# BMS_MCUV1_1.net
KiCad netlist of a schematic drawn in EAGLE
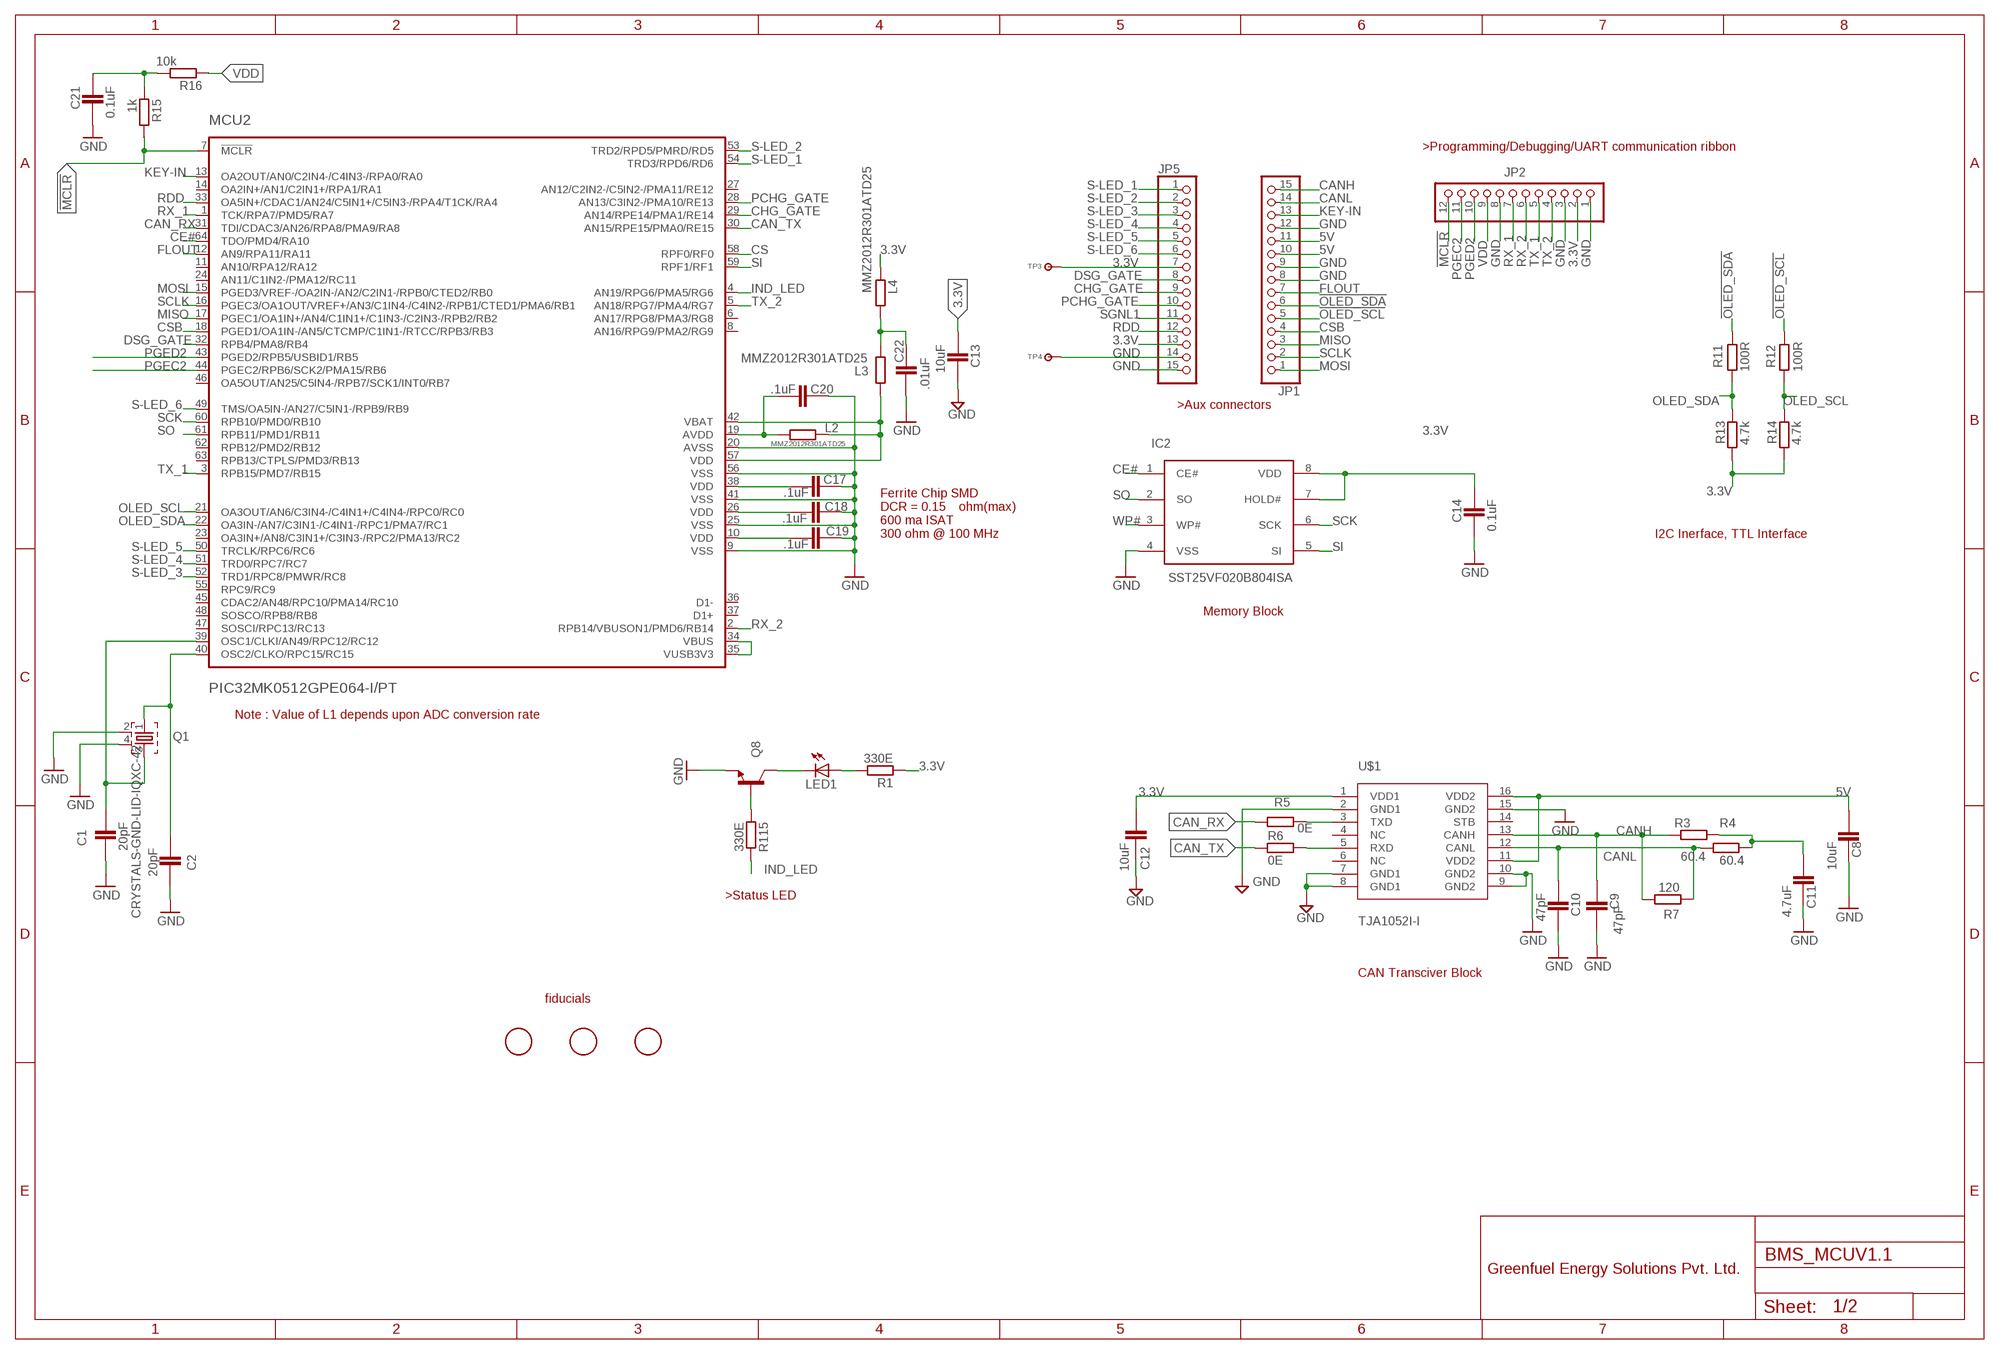
[diagram p0: schematic, sheet 1]

(export (version "E")
  (design (tool "Eeschema 10.0.6"))
  (components
    (comp (ref "C1")
      (value "20pF")
      (footprint "eagle-import:CAPC1005X60N")
      (libsource (lib "eagle-import") (part "CAPACITOR_0402"))
    )
    (comp (ref "C2")
      (value "20pF")
      (footprint "eagle-import:CAPC1005X60N")
      (libsource (lib "eagle-import") (part "CAPACITOR_0402"))
    )
    (comp (ref "C8")
      (value "10uF")
      (footprint "eagle-import:CAPC1005X60N")
      (libsource (lib "eagle-import") (part "CAPACITOR_0402"))
    )
    (comp (ref "C9")
      (value "47pF")
      (footprint "eagle-import:CAPC1005X60N")
      (libsource (lib "eagle-import") (part "CAPACITOR_0402"))
    )
    (comp (ref "C10")
      (value "47pF")
      (footprint "eagle-import:CAPC1005X60N")
      (libsource (lib "eagle-import") (part "CAPACITOR_0402"))
    )
    (comp (ref "C11")
      (value "4.7uF")
      (footprint "eagle-import:CAPC1005X60N")
      (libsource (lib "eagle-import") (part "CAPACITOR_0402"))
    )
    (comp (ref "C12")
      (value "10uF")
      (footprint "eagle-import:CAPC1005X60N")
      (libsource (lib "eagle-import") (part "CAPACITOR_0402"))
    )
    (comp (ref "C13")
      (value "10uF")
      (footprint "eagle-import:CAPC1005X60N")
      (libsource (lib "eagle-import") (part "CAPACITOR_0402"))
    )
    (comp (ref "C14")
      (value "0.1uF")
      (footprint "eagle-import:CAPC1005X60N")
      (libsource (lib "eagle-import") (part "CAPACITOR_0402"))
    )
    (comp (ref "C17")
      (value ".1uF")
      (footprint "eagle-import:CAPC1005X60N")
      (libsource (lib "eagle-import") (part "CAPACITOR_0402"))
    )
    (comp (ref "C18")
      (value ".1uF")
      (footprint "eagle-import:CAPC1005X60N")
      (libsource (lib "eagle-import") (part "CAPACITOR_0402"))
    )
    (comp (ref "C19")
      (value ".1uF")
      (footprint "eagle-import:CAPC1005X60N")
      (libsource (lib "eagle-import") (part "CAPACITOR_0402"))
    )
    (comp (ref "C20")
      (value ".1uF")
      (footprint "eagle-import:CAPC1005X60N")
      (libsource (lib "eagle-import") (part "CAPACITOR_0402"))
    )
    (comp (ref "C21")
      (value "0.1uF")
      (footprint "eagle-import:CAPC1005X60N")
      (libsource (lib "eagle-import") (part "CAPACITOR_0402"))
    )
    (comp (ref "C22")
      (value ".01uF")
      (footprint "eagle-import:CAPC1005X60N")
      (libsource (lib "eagle-import") (part "CAPACITOR_0402"))
    )
    (comp (ref "IC2")
      (value "SST25VF020B804ISA")
      (footprint "eagle-import:SOIC127P600X175-8N")
      (libsource (lib "eagle-import") (part "SST25VF020B804ISA"))
    )
    (comp (ref "JP1")
      (value "PINHD-1X15")
      (footprint "eagle-import:1X15")
      (libsource (lib "eagle-import") (part "PINHD-1X15"))
    )
    (comp (ref "JP2")
      (value "PINHD-1X12")
      (footprint "eagle-import:1X12X2")
      (libsource (lib "eagle-import") (part "PINHD-1X12"))
    )
    (comp (ref "JP5")
      (value "PINHD-1X15")
      (footprint "eagle-import:1X15")
      (libsource (lib "eagle-import") (part "PINHD-1X15"))
    )
    (comp (ref "L2")
      (value "MMZ2012R301ATD25")
      (footprint "eagle-import:RESC2012X70N")
      (libsource (lib "eagle-import") (part "RESISTOR_0805"))
    )
    (comp (ref "L3")
      (value "MMZ2012R301ATD25")
      (footprint "eagle-import:RESC2012X70N")
      (libsource (lib "eagle-import") (part "RESISTOR_0805"))
    )
    (comp (ref "L4")
      (value "MMZ2012R301ATD25")
      (footprint "eagle-import:RESC2012X70N")
      (libsource (lib "eagle-import") (part "RESISTOR_0805"))
    )
    (comp (ref "LED1")
      (value "LEDCHIP-LED0603")
      (footprint "eagle-import:CHIP-LED0603")
      (libsource (lib "eagle-import") (part "LEDCHIP-LED0603"))
    )
    (comp (ref "MCU2")
      (value "PIC32MK0512GPE064-I/PT")
      (footprint "eagle-import:TQFP-64-I_PT")
      (libsource (lib "eagle-import") (part "PIC32MK0512GPE064-I/PT"))
    )
    (comp (ref "Q1")
      (value "CRYSTALS-GND-LID-IQXC-42")
      (footprint "eagle-import:1.4X1.2-4-PAD")
      (libsource (lib "eagle-import") (part "CRYSTALS-GND-LID-IQXC-42"))
    )
    (comp (ref "Q8")
      (value "NPN_SOT-23")
      (footprint "eagle-import:SOT95P280X135-3N")
      (libsource (lib "eagle-import") (part "NPN_SOT-23"))
    )
    (comp (ref "R1")
      (value "330E")
      (footprint "eagle-import:RESC1005X40AN")
      (libsource (lib "eagle-import") (part "RESISTOR_0402"))
    )
    (comp (ref "R3")
      (value "60.4")
      (footprint "eagle-import:RESC1005X40AN")
      (libsource (lib "eagle-import") (part "RESISTOR_0402"))
    )
    (comp (ref "R4")
      (value "60.4")
      (footprint "eagle-import:RESC1005X40AN")
      (libsource (lib "eagle-import") (part "RESISTOR_0402"))
    )
    (comp (ref "R5")
      (value "0E")
      (footprint "eagle-import:RESC1005X40AN")
      (libsource (lib "eagle-import") (part "RESISTOR_0402"))
    )
    (comp (ref "R6")
      (value "0E")
      (footprint "eagle-import:RESC1005X40AN")
      (libsource (lib "eagle-import") (part "RESISTOR_0402"))
    )
    (comp (ref "R7")
      (value "120")
      (footprint "eagle-import:RESC1005X40AN")
      (libsource (lib "eagle-import") (part "RESISTOR_0402"))
    )
    (comp (ref "R11")
      (value "100R")
      (footprint "eagle-import:RESC1005X40AN")
      (libsource (lib "eagle-import") (part "RESISTOR_0402"))
    )
    (comp (ref "R12")
      (value "100R")
      (footprint "eagle-import:RESC1005X40AN")
      (libsource (lib "eagle-import") (part "RESISTOR_0402"))
    )
    (comp (ref "R13")
      (value "4.7k")
      (footprint "eagle-import:RESC1005X40AN")
      (libsource (lib "eagle-import") (part "RESISTOR_0402"))
    )
    (comp (ref "R14")
      (value "4.7k")
      (footprint "eagle-import:RESC1005X40AN")
      (libsource (lib "eagle-import") (part "RESISTOR_0402"))
    )
    (comp (ref "R15")
      (value "1k")
      (footprint "eagle-import:RESC1005X40AN")
      (libsource (lib "eagle-import") (part "RESISTOR_0402"))
    )
    (comp (ref "R16")
      (value "10k")
      (footprint "eagle-import:RESC1005X40AN")
      (libsource (lib "eagle-import") (part "RESISTOR_0402"))
    )
    (comp (ref "R115")
      (value "330E")
      (footprint "eagle-import:RESC1005X40AN")
      (libsource (lib "eagle-import") (part "RESISTOR_0402"))
    )
    (comp (ref "TP3")
      (value "TP-SMD60")
      (footprint "eagle-import:TP-SMD60")
      (libsource (lib "eagle-import") (part "TP-SMD60"))
    )
    (comp (ref "TP4")
      (value "TP-SMD60")
      (footprint "eagle-import:TP-SMD60")
      (libsource (lib "eagle-import") (part "TP-SMD60"))
    )
    (comp (ref "U$1")
      (value "TJA1052I-I")
      (footprint "eagle-import:SOT162-1")
      (libsource (lib "eagle-import") (part "TJA1052I-I"))
    )
    (comp (ref "U$2")
      (value "FIDUCIAL")
      (footprint "eagle-import:FIDUCIAL_1MM")
      (libsource (lib "eagle-import") (part "FIDUCIAL"))
    )
    (comp (ref "U$3")
      (value "FIDUCIAL")
      (footprint "eagle-import:FIDUCIAL_1MM")
      (libsource (lib "eagle-import") (part "FIDUCIAL"))
    )
    (comp (ref "U$4")
      (value "FIDUCIAL")
      (footprint "eagle-import:FIDUCIAL_1MM")
      (libsource (lib "eagle-import") (part "FIDUCIAL"))
    )
  )
  (nets
    (net (code "1") (name "3.3V") (class "Default")
      (node (ref "C12") (pin "1") (pinfunction "1_1") (pintype "passive"))
      (node (ref "C13") (pin "1") (pinfunction "1_1") (pintype "passive"))
      (node (ref "C14") (pin "1") (pinfunction "1_1") (pintype "passive"))
      (node (ref "IC2") (pin "7") (pinfunction "HOLD#_7") (pintype "input"))
      (node (ref "IC2") (pin "8") (pinfunction "VDD_8") (pintype "power_in"))
      (node (ref "JP2") (pin "2") (pinfunction "2_2") (pintype "passive"))
      (node (ref "JP5") (pin "13") (pinfunction "13_13") (pintype "passive"))
      (node (ref "JP5") (pin "7") (pinfunction "7_7") (pintype "passive"))
      (node (ref "L4") (pin "1") (pinfunction "1_1") (pintype "passive"))
      (node (ref "R1") (pin "1") (pinfunction "1_1") (pintype "passive"))
      (node (ref "R13") (pin "1") (pinfunction "1_1") (pintype "passive"))
      (node (ref "R14") (pin "1") (pinfunction "1_1") (pintype "passive"))
      (node (ref "TP3") (pin "P$1") (pinfunction "P$1_P$1") (pintype "passive"))
      (node (ref "U$1") (pin "1") (pinfunction "VDD1_1") (pintype "bidirectional"))
    )
    (net (code "2") (name "5V") (class "Default")
      (node (ref "C8") (pin "1") (pinfunction "1_1") (pintype "passive"))
      (node (ref "JP1") (pin "10") (pinfunction "10_10") (pintype "passive"))
      (node (ref "JP1") (pin "11") (pinfunction "11_11") (pintype "passive"))
      (node (ref "U$1") (pin "11") (pinfunction "VDD2_11") (pintype "bidirectional"))
      (node (ref "U$1") (pin "16") (pinfunction "VDD2_16") (pintype "bidirectional"))
    )
    (net (code "3") (name "CANH") (class "Default")
      (node (ref "C9") (pin "1") (pinfunction "1_1") (pintype "passive"))
      (node (ref "JP1") (pin "15") (pinfunction "15_15") (pintype "passive"))
      (node (ref "R3") (pin "1") (pinfunction "1_1") (pintype "passive"))
      (node (ref "R7") (pin "2") (pinfunction "2_2") (pintype "passive"))
      (node (ref "U$1") (pin "13") (pinfunction "CANH_13") (pintype "bidirectional"))
    )
    (net (code "4") (name "CANL") (class "Default")
      (node (ref "C10") (pin "1") (pinfunction "1_1") (pintype "passive"))
      (node (ref "JP1") (pin "14") (pinfunction "14_14") (pintype "passive"))
      (node (ref "R4") (pin "1") (pinfunction "1_1") (pintype "passive"))
      (node (ref "R7") (pin "1") (pinfunction "1_1") (pintype "passive"))
      (node (ref "U$1") (pin "12") (pinfunction "CANL_12") (pintype "bidirectional"))
    )
    (net (code "5") (name "CAN_RX") (class "Default")
      (node (ref "MCU2") (pin "31") (pinfunction "TDI/CDAC3/AN26/RPA8/PMA9/RA8_31") (pintype "bidirectional"))
      (node (ref "R5") (pin "1") (pinfunction "1_1") (pintype "passive"))
    )
    (net (code "6") (name "CAN_TX") (class "Default")
      (node (ref "MCU2") (pin "30") (pinfunction "AN15/RPE15/PMA0/RE15_30") (pintype "bidirectional"))
      (node (ref "R6") (pin "1") (pinfunction "1_1") (pintype "passive"))
    )
    (net (code "7") (name "CE#") (class "Default")
      (node (ref "IC2") (pin "1") (pinfunction "CE#_1") (pintype "input"))
      (node (ref "MCU2") (pin "64") (pinfunction "TDO/PMD4/RA10_64") (pintype "bidirectional"))
    )
    (net (code "8") (name "CHG_GATE") (class "Default")
      (node (ref "JP5") (pin "9") (pinfunction "9_9") (pintype "passive"))
      (node (ref "MCU2") (pin "29") (pinfunction "AN14/RPE14/PMA1/RE14_29") (pintype "bidirectional"))
    )
    (net (code "9") (name "CS") (class "Default")
      (node (ref "MCU2") (pin "58") (pinfunction "RPF0/RF0_58") (pintype "bidirectional"))
    )
    (net (code "10") (name "CSB") (class "Default")
      (node (ref "JP1") (pin "4") (pinfunction "4_4") (pintype "passive"))
      (node (ref "MCU2") (pin "18") (pinfunction "PGED1/OA1IN-/AN5/CTCMP/C1IN1-/RTCC/RPB3/RB3_18") (pintype "bidirectional"))
    )
    (net (code "11") (name "DSG_GATE") (class "Default")
      (node (ref "JP5") (pin "8") (pinfunction "8_8") (pintype "passive"))
      (node (ref "MCU2") (pin "32") (pinfunction "RPB4/PMA8/RB4_32") (pintype "bidirectional"))
    )
    (net (code "12") (name "FLOUT") (class "Default")
      (node (ref "JP1") (pin "7") (pinfunction "7_7") (pintype "passive"))
      (node (ref "MCU2") (pin "12") (pinfunction "AN9/RPA11/RA11_12") (pintype "bidirectional"))
    )
    (net (code "13") (name "GND") (class "Default")
      (node (ref "C1") (pin "2") (pinfunction "2_2") (pintype "passive"))
      (node (ref "C10") (pin "2") (pinfunction "2_2") (pintype "passive"))
      (node (ref "C11") (pin "2") (pinfunction "2_2") (pintype "passive"))
      (node (ref "C12") (pin "2") (pinfunction "2_2") (pintype "passive"))
      (node (ref "C13") (pin "2") (pinfunction "2_2") (pintype "passive"))
      (node (ref "C14") (pin "2") (pinfunction "2_2") (pintype "passive"))
      (node (ref "C17") (pin "2") (pinfunction "2_2") (pintype "passive"))
      (node (ref "C18") (pin "2") (pinfunction "2_2") (pintype "passive"))
      (node (ref "C19") (pin "2") (pinfunction "2_2") (pintype "passive"))
      (node (ref "C2") (pin "2") (pinfunction "2_2") (pintype "passive"))
      (node (ref "C20") (pin "2") (pinfunction "2_2") (pintype "passive"))
      (node (ref "C21") (pin "2") (pinfunction "2_2") (pintype "passive"))
      (node (ref "C22") (pin "1") (pinfunction "1_1") (pintype "passive"))
      (node (ref "C8") (pin "2") (pinfunction "2_2") (pintype "passive"))
      (node (ref "C9") (pin "2") (pinfunction "2_2") (pintype "passive"))
      (node (ref "IC2") (pin "4") (pinfunction "VSS_4") (pintype "power_in"))
      (node (ref "JP1") (pin "12") (pinfunction "12_12") (pintype "passive"))
      (node (ref "JP1") (pin "8") (pinfunction "8_8") (pintype "passive"))
      (node (ref "JP1") (pin "9") (pinfunction "9_9") (pintype "passive"))
      (node (ref "JP2") (pin "1") (pinfunction "1_1") (pintype "passive"))
      (node (ref "JP2") (pin "3") (pinfunction "3_3") (pintype "passive"))
      (node (ref "JP2") (pin "8") (pinfunction "8_8") (pintype "passive"))
      (node (ref "JP5") (pin "14") (pinfunction "14_14") (pintype "passive"))
      (node (ref "JP5") (pin "15") (pinfunction "15_15") (pintype "passive"))
      (node (ref "MCU2") (pin "20") (pinfunction "AVSS_20") (pintype "power_in"))
      (node (ref "MCU2") (pin "25") (pinfunction "VSS_25") (pintype "power_in"))
      (node (ref "MCU2") (pin "41") (pinfunction "VSS_41") (pintype "power_in"))
      (node (ref "MCU2") (pin "56") (pinfunction "VSS_56") (pintype "power_in"))
      (node (ref "MCU2") (pin "9") (pinfunction "VSS_9") (pintype "power_in"))
      (node (ref "Q1") (pin "2") (pinfunction "2_2") (pintype "passive"))
      (node (ref "Q1") (pin "4") (pinfunction "4_4") (pintype "passive"))
      (node (ref "Q8") (pin "2") (pinfunction "E_2") (pintype "passive"))
      (node (ref "TP4") (pin "P$1") (pinfunction "P$1_P$1") (pintype "passive"))
      (node (ref "U$1") (pin "10") (pinfunction "GND2_10") (pintype "bidirectional"))
      (node (ref "U$1") (pin "15") (pinfunction "GND2_15") (pintype "bidirectional"))
      (node (ref "U$1") (pin "2") (pinfunction "GND1_2") (pintype "bidirectional"))
      (node (ref "U$1") (pin "7") (pinfunction "GND1_7") (pintype "bidirectional"))
      (node (ref "U$1") (pin "8") (pinfunction "GND1_8") (pintype "bidirectional"))
      (node (ref "U$1") (pin "9") (pinfunction "GND2_9") (pintype "bidirectional"))
    )
    (net (code "14") (name "IND_LED") (class "Default")
      (node (ref "MCU2") (pin "4") (pinfunction "AN19/RPG6/PMA5/RG6_4") (pintype "bidirectional"))
      (node (ref "R115") (pin "2") (pinfunction "2_2") (pintype "passive"))
    )
    (net (code "15") (name "KEY-IN") (class "Default")
      (node (ref "JP1") (pin "13") (pinfunction "13_13") (pintype "passive"))
      (node (ref "MCU2") (pin "13") (pinfunction "OA2OUT/AN0/C2IN4-/C4IN3-/RPA0/RA0_13") (pintype "bidirectional"))
    )
    (net (code "16") (name "MISO") (class "Default")
      (node (ref "JP1") (pin "3") (pinfunction "3_3") (pintype "passive"))
      (node (ref "MCU2") (pin "17") (pinfunction "PGEC1/OA1IN+/AN4/C1IN1+/C1IN3-/C2IN3-/RPB2/RB2_17") (pintype "bidirectional"))
    )
    (net (code "17") (name "MOSI") (class "Default")
      (node (ref "JP1") (pin "1") (pinfunction "1_1") (pintype "passive"))
      (node (ref "MCU2") (pin "15") (pinfunction "PGED3/VREF-/OA2IN-/AN2/C2IN1-/RPB0/CTED2/RB0_15") (pintype "input"))
    )
    (net (code "18") (name "Net-(C11-Pad1)") (class "Default")
      (node (ref "C11") (pin "1") (pinfunction "1_1") (pintype "passive"))
      (node (ref "R3") (pin "2") (pinfunction "2_2") (pintype "passive"))
      (node (ref "R4") (pin "2") (pinfunction "2_2") (pintype "passive"))
    )
    (net (code "19") (name "Net-(C21-Pad1)") (class "Default")
      (node (ref "C21") (pin "1") (pinfunction "1_1") (pintype "passive"))
      (node (ref "R15") (pin "1") (pinfunction "1_1") (pintype "passive"))
      (node (ref "R16") (pin "2") (pinfunction "2_2") (pintype "passive"))
    )
    (net (code "20") (name "Net-(C22-Pad2)") (class "Default")
      (node (ref "C22") (pin "2") (pinfunction "2_2") (pintype "passive"))
      (node (ref "L3") (pin "2") (pinfunction "2_2") (pintype "passive"))
      (node (ref "L4") (pin "2") (pinfunction "2_2") (pintype "passive"))
    )
    (net (code "21") (name "Net-(LED1-PadA)") (class "Default")
      (node (ref "LED1") (pin "A") (pinfunction "A_A") (pintype "passive"))
      (node (ref "R1") (pin "2") (pinfunction "2_2") (pintype "passive"))
    )
    (net (code "22") (name "Net-(MCU2-AVDD)") (class "Default")
      (node (ref "C20") (pin "1") (pinfunction "1_1") (pintype "passive"))
      (node (ref "L2") (pin "1") (pinfunction "1_1") (pintype "passive"))
      (node (ref "MCU2") (pin "19") (pinfunction "AVDD_19") (pintype "power_in"))
    )
    (net (code "23") (name "Net-(MCU2-OSC1{slash}CLKI{slash}AN49{slash}RPC12{slash}RC12)") (class "Default")
      (node (ref "C1") (pin "1") (pinfunction "1_1") (pintype "passive"))
      (node (ref "MCU2") (pin "39") (pinfunction "OSC1/CLKI/AN49/RPC12/RC12_39") (pintype "bidirectional"))
      (node (ref "Q1") (pin "3") (pinfunction "3_3") (pintype "passive"))
    )
    (net (code "24") (name "Net-(MCU2-OSC2{slash}CLKO{slash}RPC15{slash}RC15)") (class "Default")
      (node (ref "C2") (pin "1") (pinfunction "1_1") (pintype "passive"))
      (node (ref "MCU2") (pin "40") (pinfunction "OSC2/CLKO/RPC15/RC15_40") (pintype "bidirectional"))
      (node (ref "Q1") (pin "1") (pinfunction "1_1") (pintype "passive"))
    )
    (net (code "25") (name "Net-(MCU2-VBUS)") (class "Default")
      (node (ref "MCU2") (pin "34") (pinfunction "VBUS_34") (pintype "input"))
      (node (ref "MCU2") (pin "35") (pinfunction "VUSB3V3_35") (pintype "power_in"))
    )
    (net (code "26") (name "Net-(Q8-B)") (class "Default")
      (node (ref "Q8") (pin "1") (pinfunction "B_1") (pintype "passive"))
      (node (ref "R115") (pin "1") (pinfunction "1_1") (pintype "passive"))
    )
    (net (code "27") (name "Net-(Q8-C)") (class "Default")
      (node (ref "LED1") (pin "C") (pinfunction "C_C") (pintype "passive"))
      (node (ref "Q8") (pin "3") (pinfunction "C_3") (pintype "passive"))
    )
    (net (code "28") (name "Net-(U$1-RXD)") (class "Default")
      (node (ref "R6") (pin "2") (pinfunction "2_2") (pintype "passive"))
      (node (ref "U$1") (pin "5") (pinfunction "RXD_5") (pintype "bidirectional"))
    )
    (net (code "29") (name "Net-(U$1-TXD)") (class "Default")
      (node (ref "R5") (pin "2") (pinfunction "2_2") (pintype "passive"))
      (node (ref "U$1") (pin "3") (pinfunction "TXD_3") (pintype "bidirectional"))
    )
    (net (code "30") (name "OLED_SCL") (class "Default")
      (node (ref "MCU2") (pin "21") (pinfunction "OA3OUT/AN6/C3IN4-/C4IN1+/C4IN4-/RPC0/RC0_21") (pintype "bidirectional"))
      (node (ref "R12") (pin "1") (pinfunction "1_1") (pintype "passive"))
      (node (ref "R14") (pin "2") (pinfunction "2_2") (pintype "passive"))
    )
    (net (code "31") (name "OLED_SDA") (class "Default")
      (node (ref "MCU2") (pin "22") (pinfunction "OA3IN-/AN7/C3IN1-/C4IN1-/RPC1/PMA7/RC1_22") (pintype "bidirectional"))
      (node (ref "R11") (pin "1") (pinfunction "1_1") (pintype "passive"))
      (node (ref "R13") (pin "2") (pinfunction "2_2") (pintype "passive"))
    )
    (net (code "32") (name "PCHG_GATE") (class "Default")
      (node (ref "JP5") (pin "10") (pinfunction "10_10") (pintype "passive"))
      (node (ref "MCU2") (pin "28") (pinfunction "AN13/C3IN2-/PMA10/RE13_28") (pintype "bidirectional"))
    )
    (net (code "33") (name "PGEC2") (class "Default")
      (node (ref "JP2") (pin "11") (pinfunction "11_11") (pintype "passive"))
      (node (ref "MCU2") (pin "44") (pinfunction "PGEC2/RPB6/SCK2/PMA15/RB6_44") (pintype "bidirectional"))
    )
    (net (code "34") (name "PGED2") (class "Default")
      (node (ref "JP2") (pin "10") (pinfunction "10_10") (pintype "passive"))
      (node (ref "MCU2") (pin "43") (pinfunction "PGED2/RPB5/USBID1/RB5_43") (pintype "bidirectional"))
    )
    (net (code "35") (name "RDD") (class "Default")
      (node (ref "JP5") (pin "12") (pinfunction "12_12") (pintype "passive"))
      (node (ref "MCU2") (pin "33") (pinfunction "OA5IN+/CDAC1/AN24/C5IN1+/C5IN3-/RPA4/T1CK/RA4_33") (pintype "bidirectional"))
    )
    (net (code "36") (name "RX_1") (class "Default")
      (node (ref "JP2") (pin "7") (pinfunction "7_7") (pintype "passive"))
      (node (ref "MCU2") (pin "1") (pinfunction "TCK/RPA7/PMD5/RA7_1") (pintype "bidirectional"))
    )
    (net (code "37") (name "RX_2") (class "Default")
      (node (ref "JP2") (pin "6") (pinfunction "6_6") (pintype "passive"))
      (node (ref "MCU2") (pin "2") (pinfunction "RPB14/VBUSON1/PMD6/RB14_2") (pintype "bidirectional"))
    )
    (net (code "38") (name "S-LED_1") (class "Default")
      (node (ref "JP5") (pin "1") (pinfunction "1_1") (pintype "passive"))
      (node (ref "MCU2") (pin "54") (pinfunction "TRD3/RPD6/RD6_54") (pintype "bidirectional"))
    )
    (net (code "39") (name "S-LED_2") (class "Default")
      (node (ref "JP5") (pin "2") (pinfunction "2_2") (pintype "passive"))
      (node (ref "MCU2") (pin "53") (pinfunction "TRD2/RPD5/PMRD/RD5_53") (pintype "bidirectional"))
    )
    (net (code "40") (name "S-LED_3") (class "Default")
      (node (ref "JP5") (pin "3") (pinfunction "3_3") (pintype "passive"))
      (node (ref "MCU2") (pin "52") (pinfunction "TRD1/RPC8/PMWR/RC8_52") (pintype "bidirectional"))
    )
    (net (code "41") (name "S-LED_4") (class "Default")
      (node (ref "JP5") (pin "4") (pinfunction "4_4") (pintype "passive"))
      (node (ref "MCU2") (pin "51") (pinfunction "TRD0/RPC7/RC7_51") (pintype "bidirectional"))
    )
    (net (code "42") (name "S-LED_5") (class "Default")
      (node (ref "JP5") (pin "5") (pinfunction "5_5") (pintype "passive"))
      (node (ref "MCU2") (pin "50") (pinfunction "TRCLK/RPC6/RC6_50") (pintype "bidirectional"))
    )
    (net (code "43") (name "S-LED_6") (class "Default")
      (node (ref "JP5") (pin "6") (pinfunction "6_6") (pintype "passive"))
      (node (ref "MCU2") (pin "49") (pinfunction "TMS/OA5IN-/AN27/C5IN1-/RPB9/RB9_49") (pintype "bidirectional"))
    )
    (net (code "44") (name "SCK") (class "Default")
      (node (ref "IC2") (pin "6") (pinfunction "SCK_6") (pintype "input"))
      (node (ref "MCU2") (pin "60") (pinfunction "RPB10/PMD0/RB10_60") (pintype "bidirectional"))
    )
    (net (code "45") (name "SCLK") (class "Default")
      (node (ref "JP1") (pin "2") (pinfunction "2_2") (pintype "passive"))
      (node (ref "MCU2") (pin "16") (pinfunction "PGEC3/OA1OUT/VREF+/AN3/C1IN4-/C4IN2-/RPB1/CTED1/PMA6/RB1_16") (pintype "input"))
    )
    (net (code "46") (name "SGNL1") (class "Default")
      (node (ref "JP5") (pin "11") (pinfunction "11_11") (pintype "passive"))
    )
    (net (code "47") (name "SI") (class "Default")
      (node (ref "IC2") (pin "5") (pinfunction "SI_5") (pintype "input"))
      (node (ref "MCU2") (pin "59") (pinfunction "RPF1/RF1_59") (pintype "bidirectional"))
    )
    (net (code "48") (name "SO") (class "Default")
      (node (ref "IC2") (pin "2") (pinfunction "SO_2") (pintype "output"))
      (node (ref "MCU2") (pin "61") (pinfunction "RPB11/PMD1/RB11_61") (pintype "bidirectional"))
    )
    (net (code "49") (name "TX_1") (class "Default")
      (node (ref "JP2") (pin "5") (pinfunction "5_5") (pintype "passive"))
      (node (ref "MCU2") (pin "3") (pinfunction "RPB15/PMD7/RB15_3") (pintype "bidirectional"))
    )
    (net (code "50") (name "TX_2") (class "Default")
      (node (ref "JP2") (pin "4") (pinfunction "4_4") (pintype "passive"))
      (node (ref "MCU2") (pin "5") (pinfunction "AN18/RPG7/PMA4/RG7_5") (pintype "bidirectional"))
    )
    (net (code "51") (name "VDD") (class "Default")
      (node (ref "C17") (pin "1") (pinfunction "1_1") (pintype "passive"))
      (node (ref "C18") (pin "1") (pinfunction "1_1") (pintype "passive"))
      (node (ref "C19") (pin "1") (pinfunction "1_1") (pintype "passive"))
      (node (ref "JP2") (pin "9") (pinfunction "9_9") (pintype "passive"))
      (node (ref "L2") (pin "2") (pinfunction "2_2") (pintype "passive"))
      (node (ref "L3") (pin "1") (pinfunction "1_1") (pintype "passive"))
      (node (ref "MCU2") (pin "10") (pinfunction "VDD_10") (pintype "power_in"))
      (node (ref "MCU2") (pin "26") (pinfunction "VDD_26") (pintype "power_in"))
      (node (ref "MCU2") (pin "38") (pinfunction "VDD_38") (pintype "power_in"))
      (node (ref "MCU2") (pin "42") (pinfunction "VBAT_42") (pintype "power_in"))
      (node (ref "MCU2") (pin "57") (pinfunction "VDD_57") (pintype "power_in"))
      (node (ref "R16") (pin "1") (pinfunction "1_1") (pintype "passive"))
    )
    (net (code "52") (name "WP#") (class "Default")
      (node (ref "IC2") (pin "3") (pinfunction "WP#_3") (pintype "input"))
    )
    (net (code "53") (name "unconnected-(MCU2-AN10{slash}RPA12{slash}RA12-Pad11)") (class "Default")
      (node (ref "MCU2") (pin "11") (pinfunction "AN10/RPA12/RA12_11") (pintype "bidirectional"))
    )
    (net (code "54") (name "unconnected-(MCU2-AN11{slash}C1IN2-{slash}PMA12{slash}RC11-Pad24)") (class "Default")
      (node (ref "MCU2") (pin "24") (pinfunction "AN11/C1IN2-/PMA12/RC11_24") (pintype "bidirectional"))
    )
    (net (code "55") (name "unconnected-(MCU2-AN12{slash}C2IN2-{slash}C5IN2-{slash}PMA11{slash}RE12-Pad27)") (class "Default")
      (node (ref "MCU2") (pin "27") (pinfunction "AN12/C2IN2-/C5IN2-/PMA11/RE12_27") (pintype "bidirectional"))
    )
    (net (code "56") (name "unconnected-(MCU2-AN16{slash}RPG9{slash}PMA2{slash}RG9-Pad8)") (class "Default")
      (node (ref "MCU2") (pin "8") (pinfunction "AN16/RPG9/PMA2/RG9_8") (pintype "bidirectional"))
    )
    (net (code "57") (name "unconnected-(MCU2-AN17{slash}RPG8{slash}PMA3{slash}RG8-Pad6)") (class "Default")
      (node (ref "MCU2") (pin "6") (pinfunction "AN17/RPG8/PMA3/RG8_6") (pintype "bidirectional"))
    )
    (net (code "58") (name "unconnected-(MCU2-CDAC2{slash}AN48{slash}RPC10{slash}PMA14{slash}RC10-Pad45)") (class "Default")
      (node (ref "MCU2") (pin "45") (pinfunction "CDAC2/AN48/RPC10/PMA14/RC10_45") (pintype "bidirectional"))
    )
    (net (code "59") (name "unconnected-(MCU2-D1+-Pad37)") (class "Default")
      (node (ref "MCU2") (pin "37") (pinfunction "D1+_37") (pintype "bidirectional"))
    )
    (net (code "60") (name "unconnected-(MCU2-D1--Pad36)") (class "Default")
      (node (ref "MCU2") (pin "36") (pinfunction "D1-_36") (pintype "bidirectional"))
    )
    (net (code "61") (name "unconnected-(MCU2-OA2IN+{slash}AN1{slash}C2IN1+{slash}RPA1{slash}RA1-Pad14)") (class "Default")
      (node (ref "MCU2") (pin "14") (pinfunction "OA2IN+/AN1/C2IN1+/RPA1/RA1_14") (pintype "bidirectional"))
    )
    (net (code "62") (name "unconnected-(MCU2-OA3IN+{slash}AN8{slash}C3IN1+{slash}C3IN3-{slash}RPC2{slash}PMA13{slash}RC2-Pad23)") (class "Default")
      (node (ref "MCU2") (pin "23") (pinfunction "OA3IN+/AN8/C3IN1+/C3IN3-/RPC2/PMA13/RC2_23") (pintype "bidirectional"))
    )
    (net (code "63") (name "unconnected-(MCU2-OA5OUT{slash}AN25{slash}C5IN4-{slash}RPB7{slash}SCK1{slash}INT0{slash}RB7-Pad46)") (class "Default")
      (node (ref "MCU2") (pin "46") (pinfunction "OA5OUT/AN25/C5IN4-/RPB7/SCK1/INT0/RB7_46") (pintype "bidirectional"))
    )
    (net (code "64") (name "unconnected-(MCU2-RPB12{slash}PMD2{slash}RB12-Pad62)") (class "Default")
      (node (ref "MCU2") (pin "62") (pinfunction "RPB12/PMD2/RB12_62") (pintype "bidirectional"))
    )
    (net (code "65") (name "unconnected-(MCU2-RPB13{slash}CTPLS{slash}PMD3{slash}RB13-Pad63)") (class "Default")
      (node (ref "MCU2") (pin "63") (pinfunction "RPB13/CTPLS/PMD3/RB13_63") (pintype "bidirectional"))
    )
    (net (code "66") (name "unconnected-(MCU2-RPC9{slash}RC9-Pad55)") (class "Default")
      (node (ref "MCU2") (pin "55") (pinfunction "RPC9/RC9_55") (pintype "bidirectional"))
    )
    (net (code "67") (name "unconnected-(MCU2-SOSCI{slash}RPC13{slash}RC13-Pad47)") (class "Default")
      (node (ref "MCU2") (pin "47") (pinfunction "SOSCI/RPC13/RC13_47") (pintype "bidirectional"))
    )
    (net (code "68") (name "unconnected-(MCU2-SOSCO{slash}RPB8{slash}RB8-Pad48)") (class "Default")
      (node (ref "MCU2") (pin "48") (pinfunction "SOSCO/RPB8/RB8_48") (pintype "bidirectional"))
    )
    (net (code "69") (name "unconnected-(U$1-NC-Pad4)") (class "Default")
      (node (ref "U$1") (pin "4") (pinfunction "NC_4") (pintype "bidirectional"))
    )
    (net (code "70") (name "unconnected-(U$1-NC-Pad6)") (class "Default")
      (node (ref "U$1") (pin "6") (pinfunction "NC_6") (pintype "bidirectional"))
    )
    (net (code "71") (name "unconnected-(U$1-STB-Pad14)") (class "Default")
      (node (ref "U$1") (pin "14") (pinfunction "STB_14") (pintype "bidirectional"))
    )
    (net (code "72") (name "~{MCLR}") (class "Default")
      (node (ref "JP2") (pin "12") (pinfunction "12_12") (pintype "passive"))
      (node (ref "MCU2") (pin "7") (pinfunction "~{MCLR}_7") (pintype "input"))
      (node (ref "R15") (pin "2") (pinfunction "2_2") (pintype "passive"))
    )
    (net (code "73") (name "~{OLED_SCL}") (class "Default")
      (node (ref "JP1") (pin "5") (pinfunction "5_5") (pintype "passive"))
      (node (ref "R12") (pin "2") (pinfunction "2_2") (pintype "passive"))
    )
    (net (code "74") (name "~{OLED_SDA}") (class "Default")
      (node (ref "JP1") (pin "6") (pinfunction "6_6") (pintype "passive"))
      (node (ref "R11") (pin "2") (pinfunction "2_2") (pintype "passive"))
    )
  )
)
